# VU-Meter.net
KiCad netlist of a schematic drawn in EAGLE
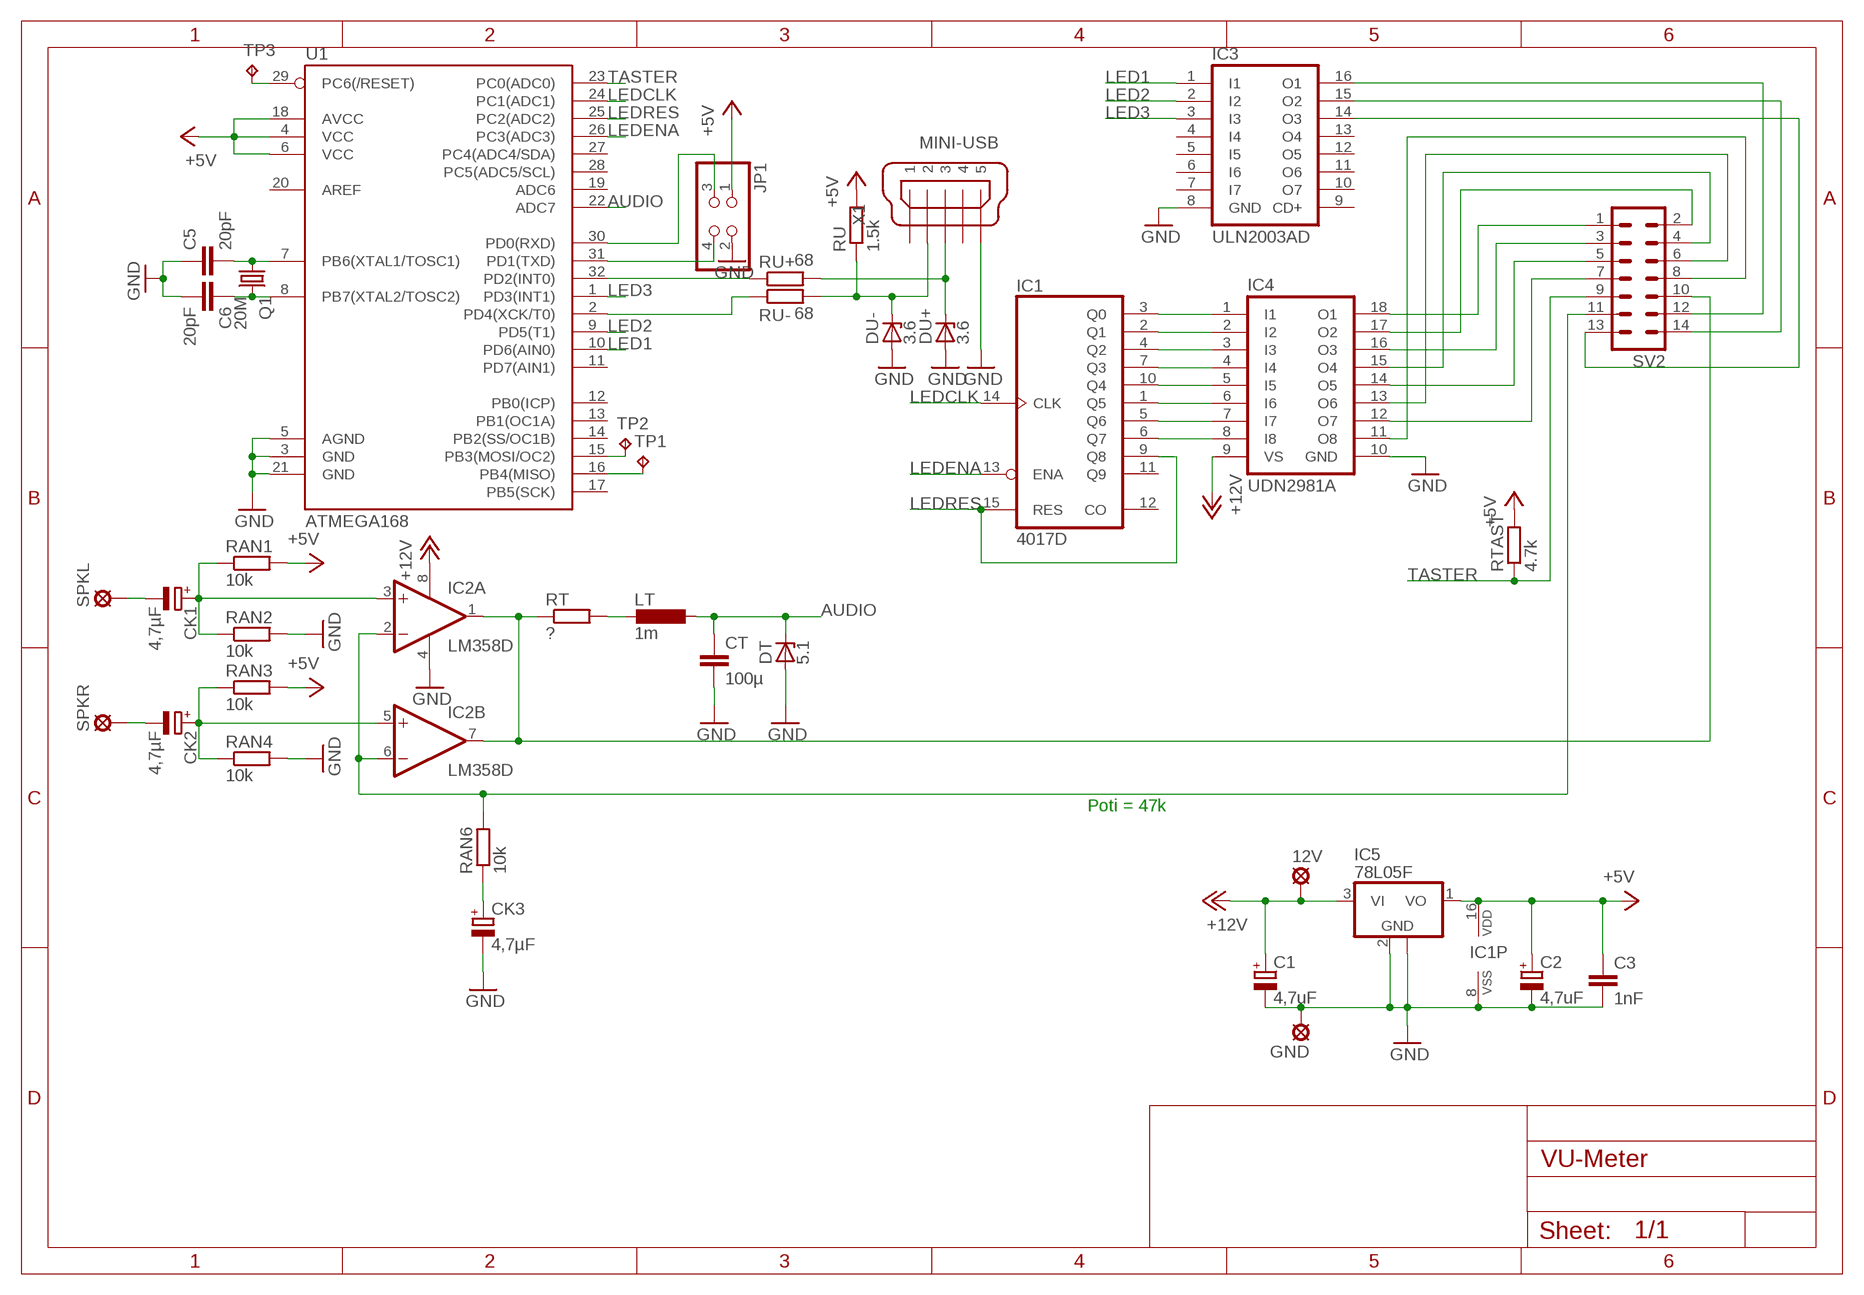
[diagram p0: schematic, sheet 1]

(export (version "E")
  (design (tool "Eeschema 10.0.6"))
  (components
    (comp (ref "12V")
      (value "LSP13")
      (footprint "eagle-import:LSP13")
      (libsource (lib "eagle-import") (part "LSP13"))
    )
    (comp (ref "C1")
      (value "4,7uF")
      (footprint "eagle-import:153CLV-0405")
      (libsource (lib "eagle-import") (part "CPOL-EU153CLV-0405"))
    )
    (comp (ref "C2")
      (value "4,7uF")
      (footprint "eagle-import:153CLV-0405")
      (libsource (lib "eagle-import") (part "CPOL-EU153CLV-0405"))
    )
    (comp (ref "C3")
      (value "1nF")
      (footprint "eagle-import:C0805K")
      (libsource (lib "eagle-import") (part "resistor_C-EUC0805K"))
    )
    (comp (ref "C5")
      (value "20pF")
      (footprint "eagle-import:C0805K")
      (libsource (lib "eagle-import") (part "C-EUC0805K"))
    )
    (comp (ref "C6")
      (value "20pF")
      (footprint "eagle-import:C0805K")
      (libsource (lib "eagle-import") (part "C-EUC0805K"))
    )
    (comp (ref "CK1")
      (value "4,7µF")
      (footprint "eagle-import:153CLV-0405")
      (libsource (lib "eagle-import") (part "CPOL-EU153CLV-0405"))
    )
    (comp (ref "CK2")
      (value "4,7µF")
      (footprint "eagle-import:153CLV-0405")
      (libsource (lib "eagle-import") (part "CPOL-EU153CLV-0405"))
    )
    (comp (ref "CK3")
      (value "4,7µF")
      (footprint "eagle-import:153CLV-0405")
      (libsource (lib "eagle-import") (part "CPOL-EU153CLV-0405"))
    )
    (comp (ref "CT")
      (value "100µ")
      (footprint "eagle-import:C1210K")
      (libsource (lib "eagle-import") (part "C-EUC1210K"))
    )
    (comp (ref "DT")
      (value "5.1")
      (footprint "eagle-import:SOD80C")
      (libsource (lib "eagle-import") (part "ZENER-DIODESOD80C"))
    )
    (comp (ref "DU+")
      (value "3.6")
      (footprint "eagle-import:SOD80C")
      (libsource (lib "eagle-import") (part "ZENER-DIODESOD80C"))
    )
    (comp (ref "DU-")
      (value "3.6")
      (footprint "eagle-import:SOD80C")
      (libsource (lib "eagle-import") (part "ZENER-DIODESOD80C"))
    )
    (comp (ref "GND")
      (value "LSP13")
      (footprint "eagle-import:LSP13")
      (libsource (lib "eagle-import") (part "LSP13"))
    )
    (comp (ref "IC1")
      (value "4017D")
      (footprint "eagle-import:SO16")
      (libsource (lib "eagle-import") (part "4017D"))
    )
    (comp (ref "IC2")
      (value "LM358D")
      (footprint "eagle-import:SO08")
      (libsource (lib "eagle-import") (part "LM358D"))
    )
    (comp (ref "IC3")
      (value "ULN2003AD")
      (footprint "eagle-import:SO16")
      (libsource (lib "eagle-import") (part "ULN2003AD"))
    )
    (comp (ref "IC4")
      (value "UDN2981A")
      (footprint "eagle-import:DIL18")
      (libsource (lib "eagle-import") (part "UDN298A1"))
    )
    (comp (ref "IC5")
      (value "78L05F")
      (footprint "eagle-import:SOT89")
      (libsource (lib "eagle-import") (part "78LF05"))
    )
    (comp (ref "JP1")
      (value "PINHD-2X2/90")
      (footprint "eagle-import:2X02_90")
      (libsource (lib "eagle-import") (part "PINHD-2X2/90"))
    )
    (comp (ref "LT")
      (value "1m")
      (footprint "eagle-import:PIS2816")
      (libsource (lib "eagle-import") (part "L-EUPIS2816"))
    )
    (comp (ref "Q1")
      (value "20M")
      (footprint "eagle-import:SM49")
      (libsource (lib "eagle-import") (part "CRYSTALSM49"))
    )
    (comp (ref "RAN1")
      (value "10k")
      (footprint "eagle-import:R0603")
      (libsource (lib "eagle-import") (part "R-EU_R0603"))
    )
    (comp (ref "RAN2")
      (value "10k")
      (footprint "eagle-import:R0603")
      (libsource (lib "eagle-import") (part "R-EU_R0603"))
    )
    (comp (ref "RAN3")
      (value "10k")
      (footprint "eagle-import:R0603")
      (libsource (lib "eagle-import") (part "R-EU_R0603"))
    )
    (comp (ref "RAN4")
      (value "10k")
      (footprint "eagle-import:R0603")
      (libsource (lib "eagle-import") (part "R-EU_R0603"))
    )
    (comp (ref "RAN6")
      (value "10k")
      (footprint "eagle-import:R0603")
      (libsource (lib "eagle-import") (part "R-EU_R0603"))
    )
    (comp (ref "RT")
      (value "?")
      (footprint "eagle-import:R0603")
      (libsource (lib "eagle-import") (part "R-EU_R0603"))
    )
    (comp (ref "RTAST")
      (value "4.7k")
      (footprint "eagle-import:R0603")
      (libsource (lib "eagle-import") (part "R-EU_R0603"))
    )
    (comp (ref "RU")
      (value "1.5k")
      (footprint "eagle-import:R0603")
      (libsource (lib "eagle-import") (part "R-EU_R0603"))
    )
    (comp (ref "RU+")
      (value "68")
      (footprint "eagle-import:R0603")
      (libsource (lib "eagle-import") (part "R-EU_R0603"))
    )
    (comp (ref "RU-")
      (value "68")
      (footprint "eagle-import:R0603")
      (libsource (lib "eagle-import") (part "R-EU_R0603"))
    )
    (comp (ref "SPKL")
      (value "LSP13")
      (footprint "eagle-import:LSP13")
      (libsource (lib "eagle-import") (part "LSP13"))
    )
    (comp (ref "SPKR")
      (value "LSP13")
      (footprint "eagle-import:LSP13")
      (libsource (lib "eagle-import") (part "LSP13"))
    )
    (comp (ref "SV2")
      (value "ML14")
      (footprint "eagle-import:ML14")
      (libsource (lib "eagle-import") (part "ML14"))
    )
    (comp (ref "TP1")
      (value "TPB1,27")
      (footprint "eagle-import:B1,27")
      (libsource (lib "eagle-import") (part "TPB1,27"))
    )
    (comp (ref "TP2")
      (value "TPB1,27")
      (footprint "eagle-import:B1,27")
      (libsource (lib "eagle-import") (part "TPB1,27"))
    )
    (comp (ref "TP3")
      (value "TPB1,27")
      (footprint "eagle-import:B1,27")
      (libsource (lib "eagle-import") (part "TPB1,27"))
    )
    (comp (ref "U1")
      (value "ATMEGA168")
      (footprint "eagle-import:TQFP32-08")
      (libsource (lib "eagle-import") (part "ATMEGA168"))
    )
    (comp (ref "X1")
      (value "MINI-USB")
      (footprint "eagle-import:32005-400")
      (libsource (lib "eagle-import") (part "MINI-USB_SHIELD5P4-32005-400"))
    )
  )
  (nets
    (net (code "1") (name "+5V") (class "Default")
      (node (ref "C2") (pin "+") (pinfunction "+_+") (pintype "passive"))
      (node (ref "C3") (pin "1") (pinfunction "1_1") (pintype "passive"))
      (node (ref "IC1") (pin "16") (pinfunction "VDD_16") (pintype "power_in"))
      (node (ref "IC5") (pin "1") (pinfunction "VO_1") (pintype "passive"))
      (node (ref "JP1") (pin "1") (pinfunction "1_1") (pintype "passive"))
      (node (ref "RAN1") (pin "2") (pinfunction "2_2") (pintype "passive"))
      (node (ref "RAN3") (pin "2") (pinfunction "2_2") (pintype "passive"))
      (node (ref "RTAST") (pin "2") (pinfunction "2_2") (pintype "passive"))
      (node (ref "RU") (pin "2") (pinfunction "2_2") (pintype "passive"))
      (node (ref "U1") (pin "18") (pinfunction "AVCC_18") (pintype "bidirectional"))
      (node (ref "U1") (pin "4") (pinfunction "VCC_4") (pintype "bidirectional"))
      (node (ref "U1") (pin "6") (pinfunction "VCC_6") (pintype "bidirectional"))
    )
    (net (code "2") (name "+12V") (class "Default")
      (node (ref "12V") (pin "MP") (pinfunction "MP_MP") (pintype "passive"))
      (node (ref "C1") (pin "+") (pinfunction "+_+") (pintype "passive"))
      (node (ref "IC2") (pin "8") (pinfunction "V+_8") (pintype "power_in"))
      (node (ref "IC4") (pin "9") (pinfunction "VS_9") (pintype "passive"))
      (node (ref "IC5") (pin "3") (pinfunction "VI_3") (pintype "input"))
    )
    (net (code "3") (name "/AUDIO") (class "Default")
      (node (ref "CT") (pin "1") (pinfunction "1_1") (pintype "passive"))
      (node (ref "DT") (pin "C") (pinfunction "C_C") (pintype "passive"))
      (node (ref "LT") (pin "1") (pinfunction "1_1") (pintype "passive"))
      (node (ref "U1") (pin "22") (pinfunction "ADC7_22") (pintype "bidirectional"))
    )
    (net (code "4") (name "/LED1") (class "Default")
      (node (ref "IC3") (pin "1") (pinfunction "I1_1") (pintype "input"))
      (node (ref "U1") (pin "10") (pinfunction "PD6(AIN0)_10") (pintype "bidirectional"))
    )
    (net (code "5") (name "/LED2") (class "Default")
      (node (ref "IC3") (pin "2") (pinfunction "I2_2") (pintype "input"))
      (node (ref "U1") (pin "9") (pinfunction "PD5(T1)_9") (pintype "bidirectional"))
    )
    (net (code "6") (name "/LED3") (class "Default")
      (node (ref "IC3") (pin "3") (pinfunction "I3_3") (pintype "input"))
      (node (ref "U1") (pin "1") (pinfunction "PD3(INT1)_1") (pintype "bidirectional"))
    )
    (net (code "7") (name "/LEDCLK") (class "Default")
      (node (ref "IC1") (pin "14") (pinfunction "CLK_14") (pintype "input"))
      (node (ref "U1") (pin "24") (pinfunction "PC1(ADC1)_24") (pintype "bidirectional"))
    )
    (net (code "8") (name "/LEDENA") (class "Default")
      (node (ref "IC1") (pin "13") (pinfunction "ENA_13") (pintype "input"))
      (node (ref "U1") (pin "26") (pinfunction "PC3(ADC3)_26") (pintype "bidirectional"))
    )
    (net (code "9") (name "/LEDRES") (class "Default")
      (node (ref "IC1") (pin "15") (pinfunction "RES_15") (pintype "input"))
      (node (ref "IC1") (pin "9") (pinfunction "Q8_9") (pintype "output"))
      (node (ref "U1") (pin "25") (pinfunction "PC2(ADC2)_25") (pintype "bidirectional"))
    )
    (net (code "10") (name "/TASTER") (class "Default")
      (node (ref "RTAST") (pin "1") (pinfunction "1_1") (pintype "passive"))
      (node (ref "SV2") (pin "9") (pinfunction "9_9") (pintype "passive"))
      (node (ref "U1") (pin "23") (pinfunction "PC0(ADC0)_23") (pintype "bidirectional"))
    )
    (net (code "11") (name "GND") (class "Default")
      (node (ref "C1") (pin "-") (pinfunction "-_-") (pintype "passive"))
      (node (ref "C2") (pin "-") (pinfunction "-_-") (pintype "passive"))
      (node (ref "C3") (pin "2") (pinfunction "2_2") (pintype "passive"))
      (node (ref "C5") (pin "1") (pinfunction "1_1") (pintype "passive"))
      (node (ref "C6") (pin "2") (pinfunction "2_2") (pintype "passive"))
      (node (ref "CK3") (pin "-") (pinfunction "-_-") (pintype "passive"))
      (node (ref "CT") (pin "2") (pinfunction "2_2") (pintype "passive"))
      (node (ref "DT") (pin "A") (pinfunction "A_A") (pintype "passive"))
      (node (ref "DU+") (pin "A") (pinfunction "A_A") (pintype "passive"))
      (node (ref "DU-") (pin "A") (pinfunction "A_A") (pintype "passive"))
      (node (ref "GND") (pin "MP") (pinfunction "MP_MP") (pintype "passive"))
      (node (ref "IC1") (pin "8") (pinfunction "VSS_8") (pintype "power_in"))
      (node (ref "IC2") (pin "4") (pinfunction "V-_4") (pintype "power_in"))
      (node (ref "IC3") (pin "8") (pinfunction "GND_8") (pintype "power_in"))
      (node (ref "IC4") (pin "10") (pinfunction "GND_10") (pintype "power_in"))
      (node (ref "IC5") (pin "2") (pinfunction "GND_2") (pintype "passive"))
      (node (ref "IC5") (pin "2@1") (pinfunction "GND_2@1") (pintype "passive"))
      (node (ref "JP1") (pin "2") (pinfunction "2_2") (pintype "passive"))
      (node (ref "RAN2") (pin "2") (pinfunction "2_2") (pintype "passive"))
      (node (ref "RAN4") (pin "2") (pinfunction "2_2") (pintype "passive"))
      (node (ref "U1") (pin "21") (pinfunction "GND_21") (pintype "bidirectional"))
      (node (ref "U1") (pin "3") (pinfunction "GND_3") (pintype "bidirectional"))
      (node (ref "U1") (pin "5") (pinfunction "AGND_5") (pintype "bidirectional"))
      (node (ref "X1") (pin "5") (pinfunction "5_5") (pintype "passive"))
    )
    (net (code "12") (name "Net-(CK1-Pad-)") (class "Default")
      (node (ref "CK1") (pin "-") (pinfunction "-_-") (pintype "passive"))
      (node (ref "SPKL") (pin "MP") (pinfunction "MP_MP") (pintype "passive"))
    )
    (net (code "13") (name "Net-(CK2-Pad-)") (class "Default")
      (node (ref "CK2") (pin "-") (pinfunction "-_-") (pintype "passive"))
      (node (ref "SPKR") (pin "MP") (pinfunction "MP_MP") (pintype "passive"))
    )
    (net (code "14") (name "Net-(CK3-Pad+)") (class "Default")
      (node (ref "CK3") (pin "+") (pinfunction "+_+") (pintype "passive"))
      (node (ref "RAN6") (pin "1") (pinfunction "1_1") (pintype "passive"))
    )
    (net (code "15") (name "Net-(DU+-PadC)") (class "Default")
      (node (ref "DU+") (pin "C") (pinfunction "C_C") (pintype "passive"))
      (node (ref "RU+") (pin "2") (pinfunction "2_2") (pintype "passive"))
      (node (ref "X1") (pin "3") (pinfunction "3_3") (pintype "passive"))
    )
    (net (code "16") (name "Net-(DU--PadC)") (class "Default")
      (node (ref "DU-") (pin "C") (pinfunction "C_C") (pintype "passive"))
      (node (ref "RU") (pin "1") (pinfunction "1_1") (pintype "passive"))
      (node (ref "RU-") (pin "2") (pinfunction "2_2") (pintype "passive"))
      (node (ref "X1") (pin "2") (pinfunction "2_2") (pintype "passive"))
    )
    (net (code "17") (name "Net-(IC1A-Q0)") (class "Default")
      (node (ref "IC1") (pin "3") (pinfunction "Q0_3") (pintype "output"))
      (node (ref "IC4") (pin "1") (pinfunction "I1_1") (pintype "input"))
    )
    (net (code "18") (name "Net-(IC1A-Q1)") (class "Default")
      (node (ref "IC1") (pin "2") (pinfunction "Q1_2") (pintype "output"))
      (node (ref "IC4") (pin "2") (pinfunction "I2_2") (pintype "input"))
    )
    (net (code "19") (name "Net-(IC1A-Q2)") (class "Default")
      (node (ref "IC1") (pin "4") (pinfunction "Q2_4") (pintype "output"))
      (node (ref "IC4") (pin "3") (pinfunction "I3_3") (pintype "input"))
    )
    (net (code "20") (name "Net-(IC1A-Q3)") (class "Default")
      (node (ref "IC1") (pin "7") (pinfunction "Q3_7") (pintype "output"))
      (node (ref "IC4") (pin "4") (pinfunction "I4_4") (pintype "input"))
    )
    (net (code "21") (name "Net-(IC1A-Q4)") (class "Default")
      (node (ref "IC1") (pin "10") (pinfunction "Q4_10") (pintype "output"))
      (node (ref "IC4") (pin "5") (pinfunction "I5_5") (pintype "input"))
    )
    (net (code "22") (name "Net-(IC1A-Q5)") (class "Default")
      (node (ref "IC1") (pin "1") (pinfunction "Q5_1") (pintype "output"))
      (node (ref "IC4") (pin "6") (pinfunction "I6_6") (pintype "input"))
    )
    (net (code "23") (name "Net-(IC1A-Q6)") (class "Default")
      (node (ref "IC1") (pin "5") (pinfunction "Q6_5") (pintype "output"))
      (node (ref "IC4") (pin "7") (pinfunction "I7_7") (pintype "input"))
    )
    (net (code "24") (name "Net-(IC1A-Q7)") (class "Default")
      (node (ref "IC1") (pin "6") (pinfunction "Q7_6") (pintype "output"))
      (node (ref "IC4") (pin "8") (pinfunction "I8_8") (pintype "input"))
    )
    (net (code "25") (name "Net-(IC2A-+IN)") (class "Default")
      (node (ref "CK1") (pin "+") (pinfunction "+_+") (pintype "passive"))
      (node (ref "IC2") (pin "3") (pinfunction "+IN_3") (pintype "input"))
      (node (ref "RAN1") (pin "1") (pinfunction "1_1") (pintype "passive"))
      (node (ref "RAN2") (pin "1") (pinfunction "1_1") (pintype "passive"))
    )
    (net (code "26") (name "Net-(IC2A--IN)") (class "Default")
      (node (ref "IC2") (pin "2") (pinfunction "-IN_2") (pintype "input"))
      (node (ref "IC2") (pin "6") (pinfunction "-IN_6") (pintype "input"))
      (node (ref "RAN6") (pin "2") (pinfunction "2_2") (pintype "passive"))
      (node (ref "SV2") (pin "11") (pinfunction "11_11") (pintype "passive"))
    )
    (net (code "27") (name "Net-(IC2A-OUT)") (class "Default")
      (node (ref "IC2") (pin "1") (pinfunction "OUT_1") (pintype "output"))
      (node (ref "IC2") (pin "7") (pinfunction "OUT_7") (pintype "output"))
      (node (ref "RT") (pin "1") (pinfunction "1_1") (pintype "passive"))
      (node (ref "SV2") (pin "10") (pinfunction "10_10") (pintype "passive"))
    )
    (net (code "28") (name "Net-(IC2B-+IN)") (class "Default")
      (node (ref "CK2") (pin "+") (pinfunction "+_+") (pintype "passive"))
      (node (ref "IC2") (pin "5") (pinfunction "+IN_5") (pintype "input"))
      (node (ref "RAN3") (pin "1") (pinfunction "1_1") (pintype "passive"))
      (node (ref "RAN4") (pin "1") (pinfunction "1_1") (pintype "passive"))
    )
    (net (code "29") (name "Net-(IC3-O1)") (class "Default")
      (node (ref "IC3") (pin "16") (pinfunction "O1_16") (pintype "open_collector"))
      (node (ref "SV2") (pin "12") (pinfunction "12_12") (pintype "passive"))
    )
    (net (code "30") (name "Net-(IC3-O2)") (class "Default")
      (node (ref "IC3") (pin "15") (pinfunction "O2_15") (pintype "open_collector"))
      (node (ref "SV2") (pin "14") (pinfunction "14_14") (pintype "passive"))
    )
    (net (code "31") (name "Net-(IC3-O3)") (class "Default")
      (node (ref "IC3") (pin "14") (pinfunction "O3_14") (pintype "open_collector"))
      (node (ref "SV2") (pin "13") (pinfunction "13_13") (pintype "passive"))
    )
    (net (code "32") (name "Net-(IC4-O1)") (class "Default")
      (node (ref "IC4") (pin "18") (pinfunction "O1_18") (pintype "open_collector"))
      (node (ref "SV2") (pin "1") (pinfunction "1_1") (pintype "passive"))
    )
    (net (code "33") (name "Net-(IC4-O2)") (class "Default")
      (node (ref "IC4") (pin "17") (pinfunction "O2_17") (pintype "open_collector"))
      (node (ref "SV2") (pin "2") (pinfunction "2_2") (pintype "passive"))
    )
    (net (code "34") (name "Net-(IC4-O3)") (class "Default")
      (node (ref "IC4") (pin "16") (pinfunction "O3_16") (pintype "open_collector"))
      (node (ref "SV2") (pin "3") (pinfunction "3_3") (pintype "passive"))
    )
    (net (code "35") (name "Net-(IC4-O4)") (class "Default")
      (node (ref "IC4") (pin "15") (pinfunction "O4_15") (pintype "open_collector"))
      (node (ref "SV2") (pin "4") (pinfunction "4_4") (pintype "passive"))
    )
    (net (code "36") (name "Net-(IC4-O5)") (class "Default")
      (node (ref "IC4") (pin "14") (pinfunction "O5_14") (pintype "open_collector"))
      (node (ref "SV2") (pin "5") (pinfunction "5_5") (pintype "passive"))
    )
    (net (code "37") (name "Net-(IC4-O6)") (class "Default")
      (node (ref "IC4") (pin "13") (pinfunction "O6_13") (pintype "open_collector"))
      (node (ref "SV2") (pin "6") (pinfunction "6_6") (pintype "passive"))
    )
    (net (code "38") (name "Net-(IC4-O7)") (class "Default")
      (node (ref "IC4") (pin "12") (pinfunction "O7_12") (pintype "open_collector"))
      (node (ref "SV2") (pin "7") (pinfunction "7_7") (pintype "passive"))
    )
    (net (code "39") (name "Net-(IC4-O8)") (class "Default")
      (node (ref "IC4") (pin "11") (pinfunction "O8_11") (pintype "open_collector"))
      (node (ref "SV2") (pin "8") (pinfunction "8_8") (pintype "passive"))
    )
    (net (code "40") (name "Net-(LT-Pad2)") (class "Default")
      (node (ref "LT") (pin "2") (pinfunction "2_2") (pintype "passive"))
      (node (ref "RT") (pin "2") (pinfunction "2_2") (pintype "passive"))
    )
    (net (code "41") (name "Net-(U1-PB3(MOSI{slash}OC2))") (class "Default")
      (node (ref "TP2") (pin "TP") (pinfunction "TP_TP") (pintype "input"))
      (node (ref "U1") (pin "15") (pinfunction "PB3(MOSI/OC2)_15") (pintype "bidirectional"))
    )
    (net (code "42") (name "Net-(U1-PB4(MISO))") (class "Default")
      (node (ref "TP1") (pin "TP") (pinfunction "TP_TP") (pintype "input"))
      (node (ref "U1") (pin "16") (pinfunction "PB4(MISO)_16") (pintype "bidirectional"))
    )
    (net (code "43") (name "Net-(U1-PB6(XTAL1{slash}TOSC1))") (class "Default")
      (node (ref "C5") (pin "2") (pinfunction "2_2") (pintype "passive"))
      (node (ref "Q1") (pin "1") (pinfunction "1_1") (pintype "passive"))
      (node (ref "U1") (pin "7") (pinfunction "PB6(XTAL1/TOSC1)_7") (pintype "bidirectional"))
    )
    (net (code "44") (name "Net-(U1-PB7(XTAL2{slash}TOSC2))") (class "Default")
      (node (ref "C6") (pin "1") (pinfunction "1_1") (pintype "passive"))
      (node (ref "Q1") (pin "2") (pinfunction "2_2") (pintype "passive"))
      (node (ref "U1") (pin "8") (pinfunction "PB7(XTAL2/TOSC2)_8") (pintype "bidirectional"))
    )
    (net (code "45") (name "Net-(U1-PC6({slash}RESET))") (class "Default")
      (node (ref "TP3") (pin "TP") (pinfunction "TP_TP") (pintype "input"))
      (node (ref "U1") (pin "29") (pinfunction "PC6(/RESET)_29") (pintype "bidirectional"))
    )
    (net (code "46") (name "Net-(U1-PD0(RXD))") (class "Default")
      (node (ref "JP1") (pin "3") (pinfunction "3_3") (pintype "passive"))
      (node (ref "U1") (pin "30") (pinfunction "PD0(RXD)_30") (pintype "bidirectional"))
    )
    (net (code "47") (name "Net-(U1-PD1(TXD))") (class "Default")
      (node (ref "JP1") (pin "4") (pinfunction "4_4") (pintype "passive"))
      (node (ref "U1") (pin "31") (pinfunction "PD1(TXD)_31") (pintype "bidirectional"))
    )
    (net (code "48") (name "Net-(U1-PD2(INT0))") (class "Default")
      (node (ref "RU+") (pin "1") (pinfunction "1_1") (pintype "passive"))
      (node (ref "U1") (pin "32") (pinfunction "PD2(INT0)_32") (pintype "bidirectional"))
    )
    (net (code "49") (name "Net-(U1-PD4(XCK{slash}T0))") (class "Default")
      (node (ref "RU-") (pin "1") (pinfunction "1_1") (pintype "passive"))
      (node (ref "U1") (pin "2") (pinfunction "PD4(XCK/T0)_2") (pintype "bidirectional"))
    )
    (net (code "50") (name "unconnected-(IC1A-CO-Pad12)") (class "Default")
      (node (ref "IC1") (pin "12") (pinfunction "CO_12") (pintype "output"))
    )
    (net (code "51") (name "unconnected-(IC1A-Q9-Pad11)") (class "Default")
      (node (ref "IC1") (pin "11") (pinfunction "Q9_11") (pintype "output"))
    )
    (net (code "52") (name "unconnected-(IC3-CD+-Pad9)") (class "Default")
      (node (ref "IC3") (pin "9") (pinfunction "CD+_9") (pintype "passive"))
    )
    (net (code "53") (name "unconnected-(IC3-I4-Pad4)") (class "Default")
      (node (ref "IC3") (pin "4") (pinfunction "I4_4") (pintype "input"))
    )
    (net (code "54") (name "unconnected-(IC3-I5-Pad5)") (class "Default")
      (node (ref "IC3") (pin "5") (pinfunction "I5_5") (pintype "input"))
    )
    (net (code "55") (name "unconnected-(IC3-I6-Pad6)") (class "Default")
      (node (ref "IC3") (pin "6") (pinfunction "I6_6") (pintype "input"))
    )
    (net (code "56") (name "unconnected-(IC3-I7-Pad7)") (class "Default")
      (node (ref "IC3") (pin "7") (pinfunction "I7_7") (pintype "input"))
    )
    (net (code "57") (name "unconnected-(IC3-O4-Pad13)") (class "Default")
      (node (ref "IC3") (pin "13") (pinfunction "O4_13") (pintype "open_collector"))
    )
    (net (code "58") (name "unconnected-(IC3-O5-Pad12)") (class "Default")
      (node (ref "IC3") (pin "12") (pinfunction "O5_12") (pintype "open_collector"))
    )
    (net (code "59") (name "unconnected-(IC3-O6-Pad11)") (class "Default")
      (node (ref "IC3") (pin "11") (pinfunction "O6_11") (pintype "open_collector"))
    )
    (net (code "60") (name "unconnected-(IC3-O7-Pad10)") (class "Default")
      (node (ref "IC3") (pin "10") (pinfunction "O7_10") (pintype "open_collector"))
    )
    (net (code "61") (name "unconnected-(U1-ADC6-Pad19)") (class "Default")
      (node (ref "U1") (pin "19") (pinfunction "ADC6_19") (pintype "bidirectional"))
    )
    (net (code "62") (name "unconnected-(U1-AREF-Pad20)") (class "Default")
      (node (ref "U1") (pin "20") (pinfunction "AREF_20") (pintype "bidirectional"))
    )
    (net (code "63") (name "unconnected-(U1-PB0(ICP)-Pad12)") (class "Default")
      (node (ref "U1") (pin "12") (pinfunction "PB0(ICP)_12") (pintype "bidirectional"))
    )
    (net (code "64") (name "unconnected-(U1-PB1(OC1A)-Pad13)") (class "Default")
      (node (ref "U1") (pin "13") (pinfunction "PB1(OC1A)_13") (pintype "bidirectional"))
    )
    (net (code "65") (name "unconnected-(U1-PB2(SS{slash}OC1B)-Pad14)") (class "Default")
      (node (ref "U1") (pin "14") (pinfunction "PB2(SS/OC1B)_14") (pintype "bidirectional"))
    )
    (net (code "66") (name "unconnected-(U1-PB5(SCK)-Pad17)") (class "Default")
      (node (ref "U1") (pin "17") (pinfunction "PB5(SCK)_17") (pintype "bidirectional"))
    )
    (net (code "67") (name "unconnected-(U1-PC4(ADC4{slash}SDA)-Pad27)") (class "Default")
      (node (ref "U1") (pin "27") (pinfunction "PC4(ADC4/SDA)_27") (pintype "bidirectional"))
    )
    (net (code "68") (name "unconnected-(U1-PC5(ADC5{slash}SCL)-Pad28)") (class "Default")
      (node (ref "U1") (pin "28") (pinfunction "PC5(ADC5/SCL)_28") (pintype "bidirectional"))
    )
    (net (code "69") (name "unconnected-(U1-PD7(AIN1)-Pad11)") (class "Default")
      (node (ref "U1") (pin "11") (pinfunction "PD7(AIN1)_11") (pintype "bidirectional"))
    )
    (net (code "70") (name "unconnected-(X1-Pad1)") (class "Default")
      (node (ref "X1") (pin "1") (pinfunction "1_1") (pintype "passive"))
    )
    (net (code "71") (name "unconnected-(X1-Pad4)") (class "Default")
      (node (ref "X1") (pin "4") (pinfunction "4_4") (pintype "passive"))
    )
  )
)
